# schematic.net
KiCad netlist of a schematic drawn in EAGLE
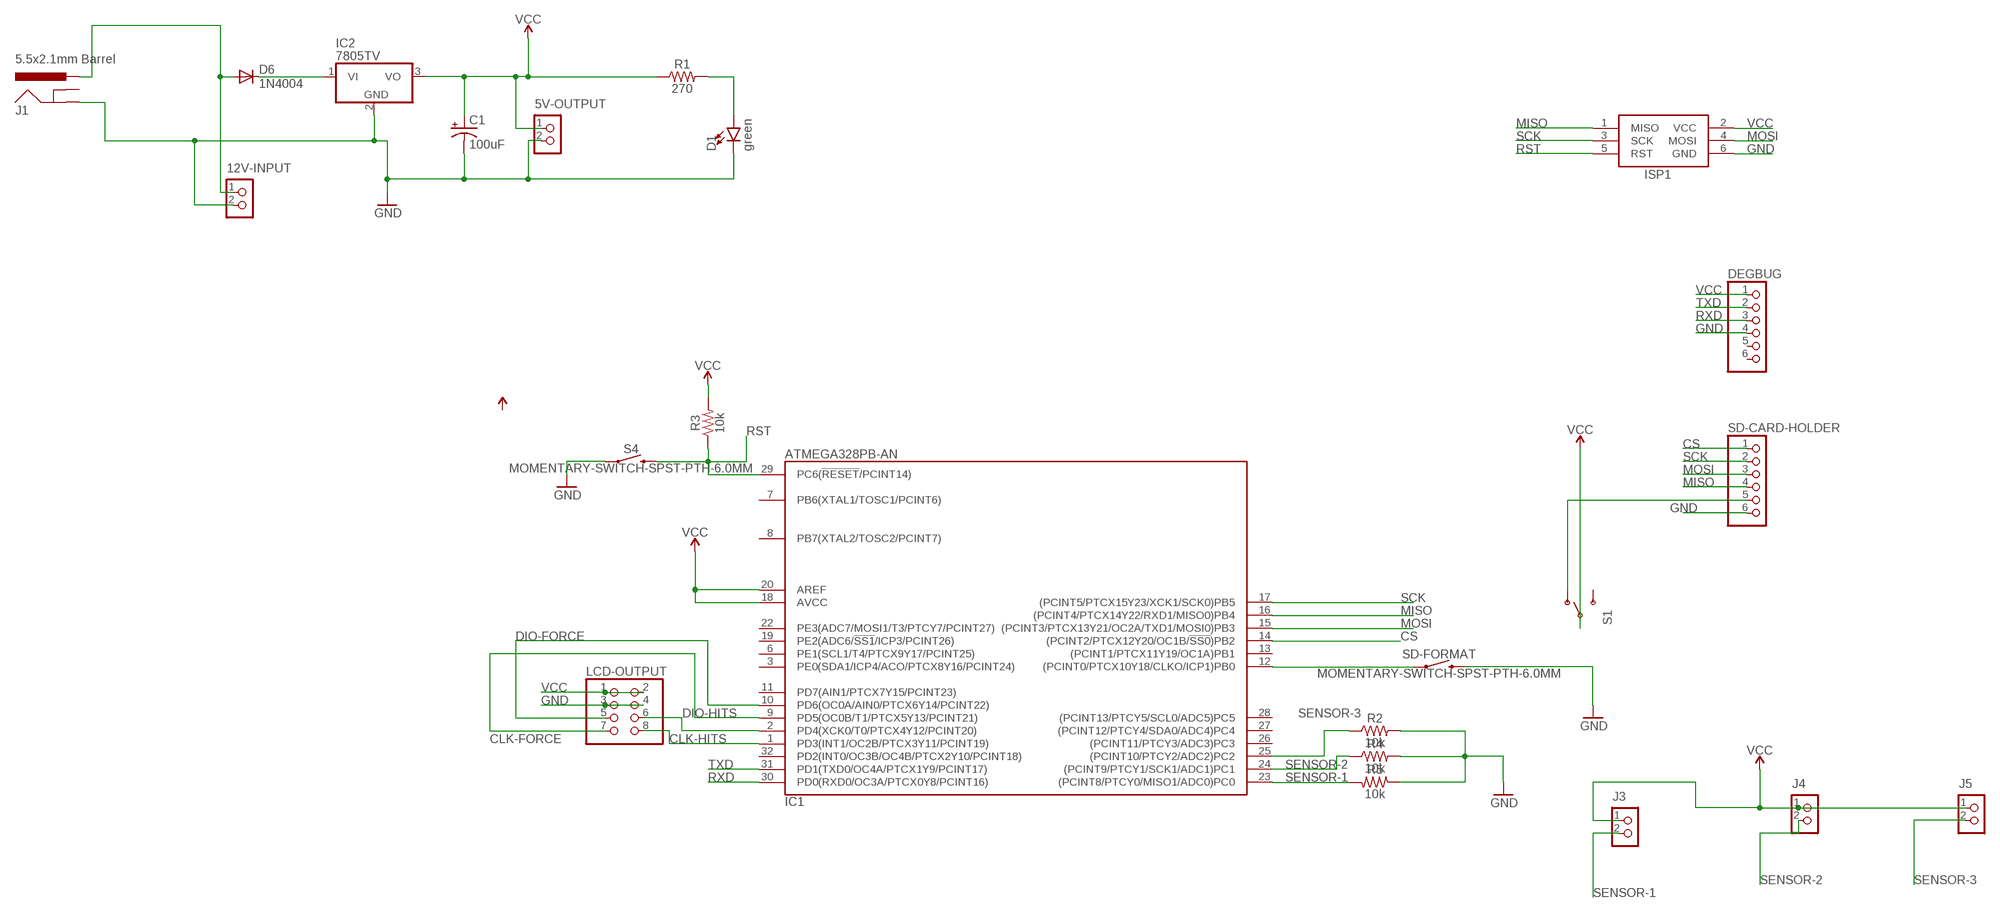
[diagram p0: schematic, sheet 1]

(export (version "E")
  (design (tool "Eeschema 10.0.6"))
  (components
    (comp (ref "5V-OUTPUT")
      (value "CON_TERMINAL_BLOCK_02-5MM")
      (footprint "eagle-import:TERMINAL_BLOCK_2P_5")
      (libsource (lib "eagle-import") (part "CON_TERMINAL_BLOCK_02-5MM"))
    )
    (comp (ref "12V-INPUT")
      (value "CON_TERMINAL_BLOCK_02-5MM")
      (footprint "eagle-import:TERMINAL_BLOCK_2P_5")
      (libsource (lib "eagle-import") (part "CON_TERMINAL_BLOCK_02-5MM"))
    )
    (comp (ref "C1")
      (value "100uF")
      (footprint "eagle-import:CPOL-RADIAL-2.5MM-6.5MM")
      (libsource (lib "eagle-import") (part "100UF-POLAR-RADIAL-2.5MM-25V-20%"))
    )
    (comp (ref "D1")
      (value "green")
      (footprint "eagle-import:LED-1206")
      (libsource (lib "eagle-import") (part "LED1206"))
    )
    (comp (ref "D6")
      (value "1N4004")
      (footprint "eagle-import:DO41-10")
      (libsource (lib "eagle-import") (part "1N4004"))
    )
    (comp (ref "DEGBUG")
      (value "PINHD-1X6")
      (footprint "eagle-import:1X06")
      (libsource (lib "eagle-import") (part "PINHD-1X6"))
    )
    (comp (ref "IC1")
      (value "ATMEGA328PB-AN")
      (footprint "eagle-import:QFP32_7X7_0.80")
      (libsource (lib "eagle-import") (part "ATMEGA328PB-AN"))
    )
    (comp (ref "IC2")
      (value "7805TV")
      (footprint "eagle-import:TO220V")
      (libsource (lib "eagle-import") (part "78TV05"))
    )
    (comp (ref "ISP1")
      (value "AVRISP-6")
      (footprint "eagle-import:AVRISP")
      (libsource (lib "eagle-import") (part "AVRISP-6"))
    )
    (comp (ref "J1")
      (value "5.5x2.1mm Barrel")
      (footprint "eagle-import:POWER_JACK_SMD")
      (libsource (lib "eagle-import") (part "POWER_JACKSMD"))
    )
    (comp (ref "J3")
      (value "CON_TERMINAL_BLOCK_02-5MM")
      (footprint "eagle-import:TERMINAL_BLOCK_2P_5")
      (libsource (lib "eagle-import") (part "CON_TERMINAL_BLOCK_02-5MM"))
    )
    (comp (ref "J4")
      (value "CON_TERMINAL_BLOCK_02-5MM")
      (footprint "eagle-import:TERMINAL_BLOCK_2P_5")
      (libsource (lib "eagle-import") (part "CON_TERMINAL_BLOCK_02-5MM"))
    )
    (comp (ref "J5")
      (value "CON_TERMINAL_BLOCK_02-5MM")
      (footprint "eagle-import:TERMINAL_BLOCK_2P_5")
      (libsource (lib "eagle-import") (part "CON_TERMINAL_BLOCK_02-5MM"))
    )
    (comp (ref "LCD-OUTPUT")
      (value "PINHD-2X4")
      (footprint "eagle-import:2X04")
      (libsource (lib "eagle-import") (part "PINHD-2X4"))
    )
    (comp (ref "R1")
      (value "270")
      (footprint "eagle-import:1206")
      (libsource (lib "eagle-import") (part "RESISTOR1206"))
    )
    (comp (ref "R2")
      (value "10k")
      (footprint "eagle-import:1206")
      (libsource (lib "eagle-import") (part "RESISTOR1206"))
    )
    (comp (ref "R3")
      (value "10k")
      (footprint "eagle-import:1206")
      (libsource (lib "eagle-import") (part "RESISTOR1206"))
    )
    (comp (ref "R4")
      (value "10k")
      (footprint "eagle-import:1206")
      (libsource (lib "eagle-import") (part "RESISTOR1206"))
    )
    (comp (ref "R5")
      (value "10k")
      (footprint "eagle-import:1206")
      (libsource (lib "eagle-import") (part "RESISTOR1206"))
    )
    (comp (ref "S1")
      (value "SWITCH-SPDTSMD")
      (footprint "eagle-import:SWITCH_SPDT_SMD")
      (libsource (lib "eagle-import") (part "SWITCH-SPDTSMD"))
    )
    (comp (ref "S4")
      (value "MOMENTARY-SWITCH-SPST-PTH-6.0MM")
      (footprint "eagle-import:TACTILE_SWITCH_PTH_6.0MM")
      (libsource (lib "eagle-import") (part "MOMENTARY-SWITCH-SPST-PTH-6.0MM"))
    )
    (comp (ref "SD-CARD-HOLDER")
      (value "PINHD-1X6")
      (footprint "eagle-import:1X06")
      (libsource (lib "eagle-import") (part "PINHD-1X6"))
    )
    (comp (ref "SD-FORMAT")
      (value "MOMENTARY-SWITCH-SPST-PTH-6.0MM")
      (footprint "eagle-import:TACTILE_SWITCH_PTH_6.0MM")
      (libsource (lib "eagle-import") (part "MOMENTARY-SWITCH-SPST-PTH-6.0MM"))
    )
  )
  (nets
    (net (code "1") (name "/CLK-FORCE") (class "Default")
      (node (ref "IC1") (pin "9") (pinfunction "PD5(OC0B/T1/PTCX5Y13/PCINT21)_9") (pintype "bidirectional"))
      (node (ref "LCD-OUTPUT") (pin "7") (pinfunction "7_7") (pintype "passive"))
    )
    (net (code "2") (name "/CLK-HITS") (class "Default")
      (node (ref "IC1") (pin "1") (pinfunction "PD3(INT1/OC2B/PTCX3Y11/PCINT19)_1") (pintype "bidirectional"))
      (node (ref "LCD-OUTPUT") (pin "8") (pinfunction "8_8") (pintype "passive"))
    )
    (net (code "3") (name "/CS") (class "Default")
      (node (ref "IC1") (pin "14") (pinfunction "(PCINT2/PTCX12Y20/OC1B/~{SS0})PB2_14") (pintype "bidirectional"))
      (node (ref "SD-CARD-HOLDER") (pin "1") (pinfunction "1_1") (pintype "passive"))
    )
    (net (code "4") (name "/DIO-FORCE") (class "Default")
      (node (ref "IC1") (pin "10") (pinfunction "PD6(OC0A/AIN0/PTCX6Y14/PCINT22)_10") (pintype "bidirectional"))
      (node (ref "LCD-OUTPUT") (pin "5") (pinfunction "5_5") (pintype "passive"))
    )
    (net (code "5") (name "/DIO-HITS") (class "Default")
      (node (ref "IC1") (pin "2") (pinfunction "PD4(XCK0/T0/PTCX4Y12/PCINT20)_2") (pintype "bidirectional"))
      (node (ref "LCD-OUTPUT") (pin "6") (pinfunction "6_6") (pintype "passive"))
    )
    (net (code "6") (name "/MISO") (class "Default")
      (node (ref "IC1") (pin "16") (pinfunction "(PCINT4/PTCX14Y22/RXD1/MISO0)PB4_16") (pintype "bidirectional"))
      (node (ref "ISP1") (pin "1") (pinfunction "MISO_1") (pintype "input"))
      (node (ref "SD-CARD-HOLDER") (pin "4") (pinfunction "4_4") (pintype "passive"))
    )
    (net (code "7") (name "/MOSI") (class "Default")
      (node (ref "IC1") (pin "15") (pinfunction "(PCINT3/PTCX13Y21/OC2A/TXD1/MOSI0)PB3_15") (pintype "bidirectional"))
      (node (ref "ISP1") (pin "4") (pinfunction "MOSI_4") (pintype "output"))
      (node (ref "SD-CARD-HOLDER") (pin "3") (pinfunction "3_3") (pintype "passive"))
    )
    (net (code "8") (name "/RST") (class "Default")
      (node (ref "IC1") (pin "29") (pinfunction "PC6(~{RESET}/PCINT14)_29") (pintype "bidirectional"))
      (node (ref "ISP1") (pin "5") (pinfunction "RST_5") (pintype "output"))
      (node (ref "R3") (pin "1") (pinfunction "1_1") (pintype "passive"))
      (node (ref "S4") (pin "3") (pinfunction "2_3") (pintype "passive"))
    )
    (net (code "9") (name "/RXD") (class "Default")
      (node (ref "DEGBUG") (pin "3") (pinfunction "3_3") (pintype "passive"))
      (node (ref "IC1") (pin "30") (pinfunction "PD0(RXD0/OC3A/PTCX0Y8/PCINT16)_30") (pintype "bidirectional"))
    )
    (net (code "10") (name "/SCK") (class "Default")
      (node (ref "IC1") (pin "17") (pinfunction "(PCINT5/PTCX15Y23/XCK1/SCK0)PB5_17") (pintype "bidirectional"))
      (node (ref "ISP1") (pin "3") (pinfunction "SCK_3") (pintype "output"))
      (node (ref "SD-CARD-HOLDER") (pin "2") (pinfunction "2_2") (pintype "passive"))
    )
    (net (code "11") (name "/SENSOR-1") (class "Default")
      (node (ref "IC1") (pin "23") (pinfunction "(PCINT8/PTCY0/MISO1/ADC0)PC0_23") (pintype "bidirectional"))
      (node (ref "J3") (pin "2") (pinfunction "2_2") (pintype "passive"))
      (node (ref "R5") (pin "2") (pinfunction "2_2") (pintype "passive"))
    )
    (net (code "12") (name "/SENSOR-2") (class "Default")
      (node (ref "IC1") (pin "24") (pinfunction "(PCINT9/PTCY1/SCK1/ADC1)PC1_24") (pintype "bidirectional"))
      (node (ref "J4") (pin "2") (pinfunction "2_2") (pintype "passive"))
      (node (ref "R4") (pin "1") (pinfunction "1_1") (pintype "passive"))
    )
    (net (code "13") (name "/SENSOR-3") (class "Default")
      (node (ref "IC1") (pin "25") (pinfunction "(PCINT10/PTCY2/ADC2)PC2_25") (pintype "bidirectional"))
      (node (ref "J5") (pin "2") (pinfunction "2_2") (pintype "passive"))
      (node (ref "R2") (pin "1") (pinfunction "1_1") (pintype "passive"))
    )
    (net (code "14") (name "/TXD") (class "Default")
      (node (ref "DEGBUG") (pin "2") (pinfunction "2_2") (pintype "passive"))
      (node (ref "IC1") (pin "31") (pinfunction "PD1(TXD0/OC4A/PTCX1Y9/PCINT17)_31") (pintype "bidirectional"))
    )
    (net (code "15") (name "GND") (class "Default")
      (node (ref "12V-INPUT") (pin "2") (pinfunction "2_2") (pintype "passive"))
      (node (ref "5V-OUTPUT") (pin "2") (pinfunction "2_2") (pintype "passive"))
      (node (ref "C1") (pin "2") (pinfunction "-_2") (pintype "passive"))
      (node (ref "D1") (pin "C") (pinfunction "C_C") (pintype "passive"))
      (node (ref "DEGBUG") (pin "4") (pinfunction "4_4") (pintype "passive"))
      (node (ref "IC2") (pin "2") (pinfunction "GND_2") (pintype "passive"))
      (node (ref "ISP1") (pin "6") (pinfunction "GND_6") (pintype "power_in"))
      (node (ref "J1") (pin "P$4") (pinfunction "GND_P$4") (pintype "bidirectional"))
      (node (ref "LCD-OUTPUT") (pin "3") (pinfunction "3_3") (pintype "passive"))
      (node (ref "LCD-OUTPUT") (pin "4") (pinfunction "4_4") (pintype "passive"))
      (node (ref "R2") (pin "2") (pinfunction "2_2") (pintype "passive"))
      (node (ref "R4") (pin "2") (pinfunction "2_2") (pintype "passive"))
      (node (ref "R5") (pin "1") (pinfunction "1_1") (pintype "passive"))
      (node (ref "S4") (pin "1") (pinfunction "1_1") (pintype "passive"))
      (node (ref "SD-CARD-HOLDER") (pin "6") (pinfunction "6_6") (pintype "passive"))
      (node (ref "SD-FORMAT") (pin "3") (pinfunction "2_3") (pintype "passive"))
    )
    (net (code "16") (name "Net-(D1-PadA)") (class "Default")
      (node (ref "D1") (pin "A") (pinfunction "A_A") (pintype "passive"))
      (node (ref "R1") (pin "2") (pinfunction "2_2") (pintype "passive"))
    )
    (net (code "17") (name "Net-(IC1A-(PCINT0{slash}PTCX10Y18{slash}CLKO{slash}ICP1)PB0)") (class "Default")
      (node (ref "IC1") (pin "12") (pinfunction "(PCINT0/PTCX10Y18/CLKO/ICP1)PB0_12") (pintype "bidirectional"))
      (node (ref "SD-FORMAT") (pin "1") (pinfunction "1_1") (pintype "passive"))
    )
    (net (code "18") (name "Net-(IC2-VI)") (class "Default")
      (node (ref "D6") (pin "C") (pinfunction "C_C") (pintype "passive"))
      (node (ref "IC2") (pin "1") (pinfunction "VI_1") (pintype "input"))
    )
    (net (code "19") (name "Net-(J1-PWR)") (class "Default")
      (node (ref "12V-INPUT") (pin "1") (pinfunction "1_1") (pintype "passive"))
      (node (ref "D6") (pin "A") (pinfunction "A_A") (pintype "passive"))
      (node (ref "J1") (pin "VIN0") (pinfunction "PWR_VIN0") (pintype "bidirectional"))
    )
    (net (code "20") (name "Net-(S1-O)") (class "Default")
      (node (ref "S1") (pin "1") (pinfunction "O_1") (pintype "passive"))
      (node (ref "SD-CARD-HOLDER") (pin "5") (pinfunction "5_5") (pintype "passive"))
    )
    (net (code "21") (name "VCC") (class "Default")
      (node (ref "5V-OUTPUT") (pin "1") (pinfunction "1_1") (pintype "passive"))
      (node (ref "C1") (pin "1") (pinfunction "+_1") (pintype "passive"))
      (node (ref "DEGBUG") (pin "1") (pinfunction "1_1") (pintype "passive"))
      (node (ref "IC1") (pin "18") (pinfunction "AVCC_18") (pintype "power_in"))
      (node (ref "IC1") (pin "20") (pinfunction "AREF_20") (pintype "passive"))
      (node (ref "IC2") (pin "3") (pinfunction "VO_3") (pintype "passive"))
      (node (ref "ISP1") (pin "2") (pinfunction "VCC_2") (pintype "power_in"))
      (node (ref "J3") (pin "1") (pinfunction "1_1") (pintype "passive"))
      (node (ref "J4") (pin "1") (pinfunction "1_1") (pintype "passive"))
      (node (ref "J5") (pin "1") (pinfunction "1_1") (pintype "passive"))
      (node (ref "LCD-OUTPUT") (pin "1") (pinfunction "1_1") (pintype "passive"))
      (node (ref "LCD-OUTPUT") (pin "2") (pinfunction "2_2") (pintype "passive"))
      (node (ref "R1") (pin "1") (pinfunction "1_1") (pintype "passive"))
      (node (ref "R3") (pin "2") (pinfunction "2_2") (pintype "passive"))
      (node (ref "S1") (pin "2") (pinfunction "P_2") (pintype "passive"))
    )
    (net (code "22") (name "unconnected-(DEGBUG-Pad5)") (class "Default")
      (node (ref "DEGBUG") (pin "5") (pinfunction "5_5") (pintype "passive"))
    )
    (net (code "23") (name "unconnected-(DEGBUG-Pad6)") (class "Default")
      (node (ref "DEGBUG") (pin "6") (pinfunction "6_6") (pintype "passive"))
    )
    (net (code "24") (name "unconnected-(IC1A-(PCINT1{slash}PTCX11Y19{slash}OC1A)PB1-Pad13)") (class "Default")
      (node (ref "IC1") (pin "13") (pinfunction "(PCINT1/PTCX11Y19/OC1A)PB1_13") (pintype "bidirectional"))
    )
    (net (code "25") (name "unconnected-(IC1A-(PCINT11{slash}PTCY3{slash}ADC3)PC3-Pad26)") (class "Default")
      (node (ref "IC1") (pin "26") (pinfunction "(PCINT11/PTCY3/ADC3)PC3_26") (pintype "bidirectional"))
    )
    (net (code "26") (name "unconnected-(IC1A-(PCINT12{slash}PTCY4{slash}SDA0{slash}ADC4)PC4-Pad27)") (class "Default")
      (node (ref "IC1") (pin "27") (pinfunction "(PCINT12/PTCY4/SDA0/ADC4)PC4_27") (pintype "bidirectional"))
    )
    (net (code "27") (name "unconnected-(IC1A-(PCINT13{slash}PTCY5{slash}SCL0{slash}ADC5)PC5-Pad28)") (class "Default")
      (node (ref "IC1") (pin "28") (pinfunction "(PCINT13/PTCY5/SCL0/ADC5)PC5_28") (pintype "bidirectional"))
    )
    (net (code "28") (name "unconnected-(IC1A-PB6(XTAL1{slash}TOSC1{slash}PCINT6)-Pad7)") (class "Default")
      (node (ref "IC1") (pin "7") (pinfunction "PB6(XTAL1/TOSC1/PCINT6)_7") (pintype "bidirectional"))
    )
    (net (code "29") (name "unconnected-(IC1A-PB7(XTAL2{slash}TOSC2{slash}PCINT7)-Pad8)") (class "Default")
      (node (ref "IC1") (pin "8") (pinfunction "PB7(XTAL2/TOSC2/PCINT7)_8") (pintype "bidirectional"))
    )
    (net (code "30") (name "unconnected-(IC1A-PD2(INT0{slash}OC3B{slash}OC4B{slash}PTCX2Y10{slash}PCINT18)-Pad32)") (class "Default")
      (node (ref "IC1") (pin "32") (pinfunction "PD2(INT0/OC3B/OC4B/PTCX2Y10/PCINT18)_32") (pintype "bidirectional"))
    )
    (net (code "31") (name "unconnected-(IC1A-PD7(AIN1{slash}PTCX7Y15{slash}PCINT23)-Pad11)") (class "Default")
      (node (ref "IC1") (pin "11") (pinfunction "PD7(AIN1/PTCX7Y15/PCINT23)_11") (pintype "bidirectional"))
    )
    (net (code "32") (name "unconnected-(IC1A-PE0(SDA1{slash}ICP4{slash}ACO{slash}PTCX8Y16{slash}PCINT24)-Pad3)") (class "Default")
      (node (ref "IC1") (pin "3") (pinfunction "PE0(SDA1/ICP4/ACO/PTCX8Y16/PCINT24)_3") (pintype "bidirectional"))
    )
    (net (code "33") (name "unconnected-(IC1A-PE1(SCL1{slash}T4{slash}PTCX9Y17{slash}PCINT25)-Pad6)") (class "Default")
      (node (ref "IC1") (pin "6") (pinfunction "PE1(SCL1/T4/PTCX9Y17/PCINT25)_6") (pintype "bidirectional"))
    )
    (net (code "34") (name "unconnected-(IC1A-PE2(ADC6{slash}~{SS1}{slash}ICP3{slash}PCINT26)-Pad19)") (class "Default")
      (node (ref "IC1") (pin "19") (pinfunction "PE2(ADC6/~{SS1}/ICP3/PCINT26)_19") (pintype "bidirectional"))
    )
    (net (code "35") (name "unconnected-(IC1A-PE3(ADC7{slash}MOSI1{slash}T3{slash}PTCY7{slash}PCINT27)-Pad22)") (class "Default")
      (node (ref "IC1") (pin "22") (pinfunction "PE3(ADC7/MOSI1/T3/PTCY7/PCINT27)_22") (pintype "bidirectional"))
    )
    (net (code "36") (name "unconnected-(J1-GNDBREAK-PadGND)") (class "Default")
      (node (ref "J1") (pin "GND") (pinfunction "GNDBREAK_GND") (pintype "bidirectional"))
    )
    (net (code "37") (name "unconnected-(S1-S-Pad3)") (class "Default")
      (node (ref "S1") (pin "3") (pinfunction "S_3") (pintype "passive"))
    )
  )
)
